# shield.net
KiCad netlist of a schematic drawn in EAGLE
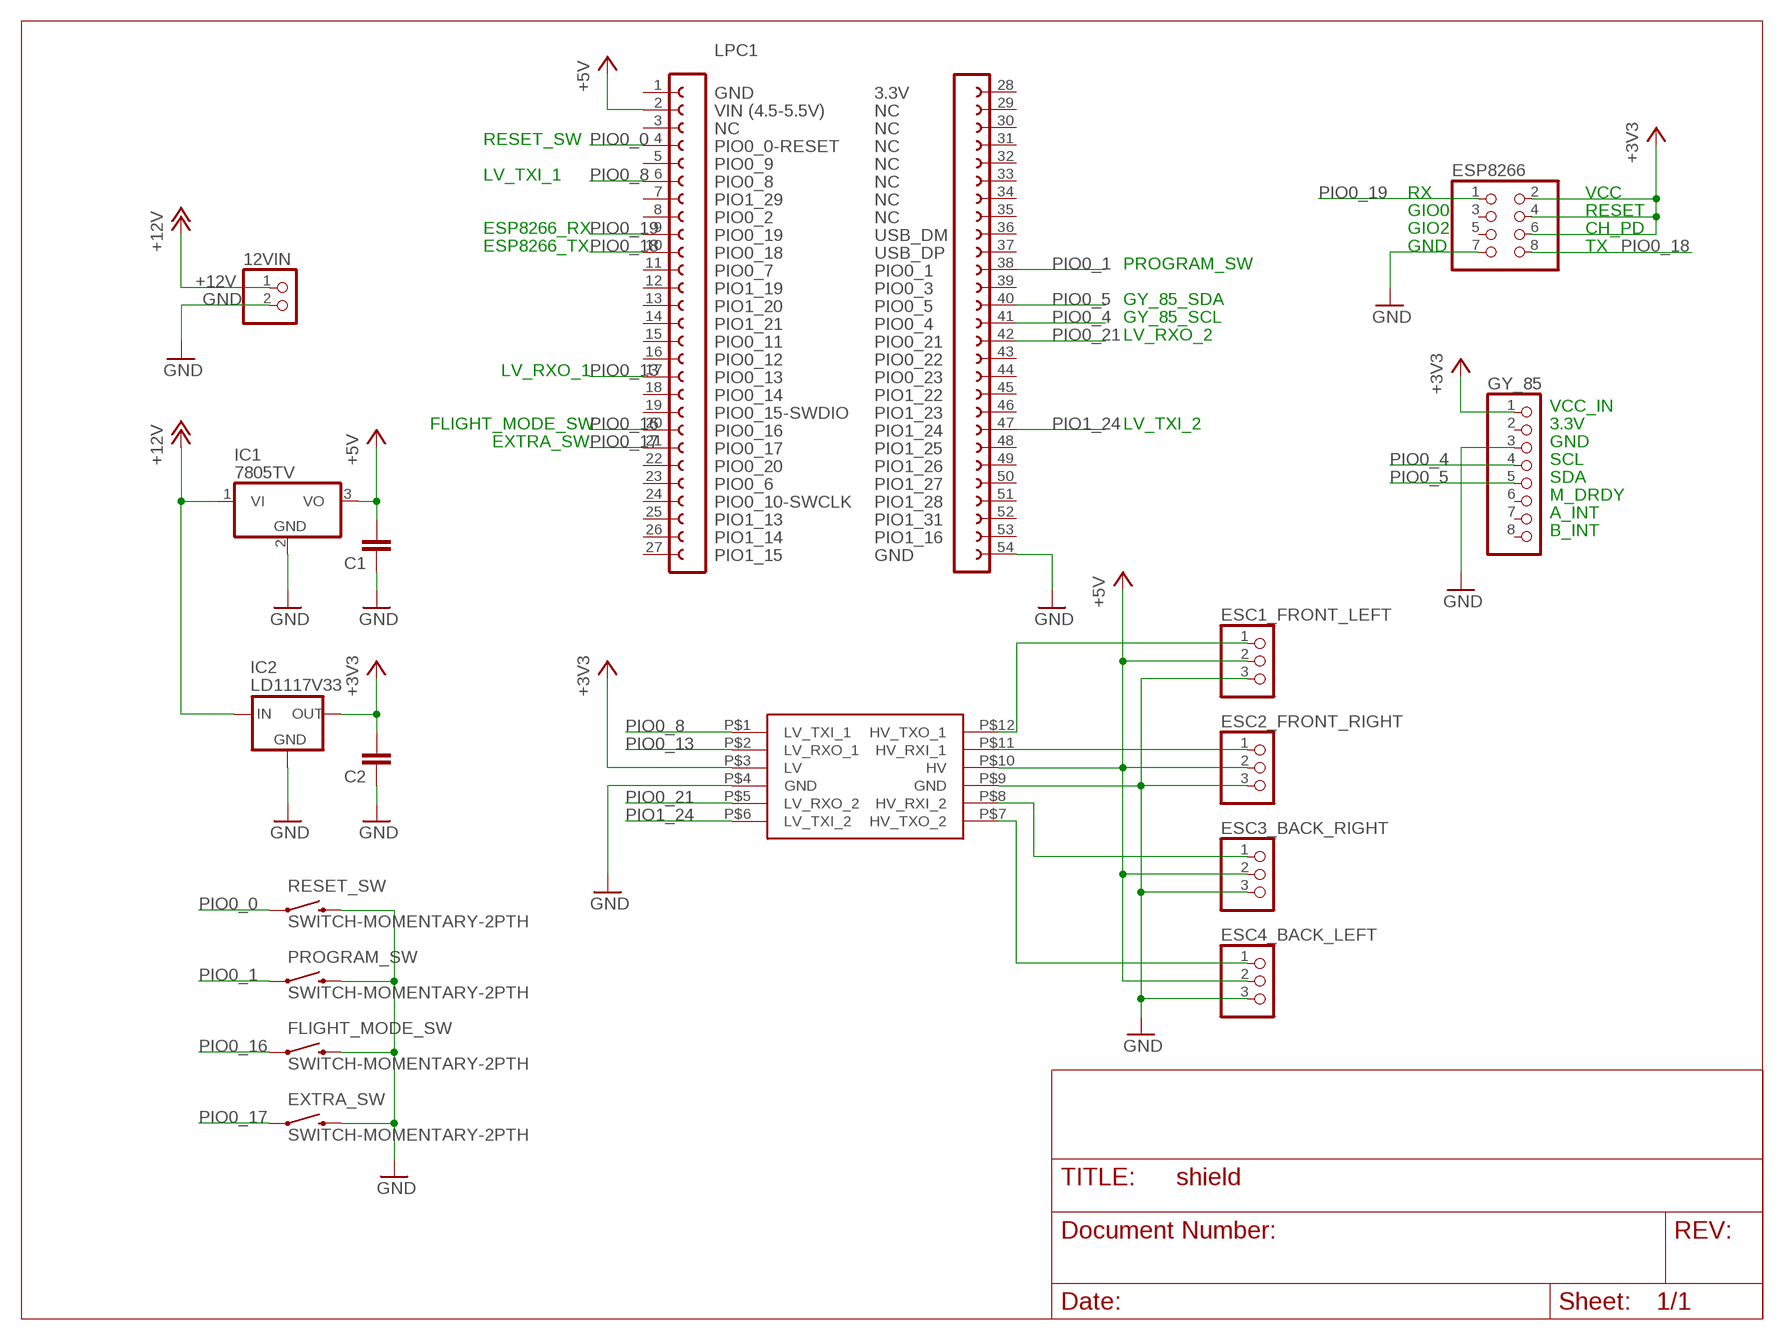
[diagram p0: schematic, sheet 1]

(export (version "E")
  (design (tool "Eeschema 10.0.6"))
  (components
    (comp (ref "12VIN")
      (value "PINHD-1X2")
      (footprint "eagle-import:1X02")
      (libsource (lib "eagle-import") (part "PINHD-1X2"))
    )
    (comp (ref "C1")
      (value "C-EU025-024X044")
      (footprint "eagle-import:C025-024X044")
      (libsource (lib "eagle-import") (part "C-EU025-024X044"))
    )
    (comp (ref "C2")
      (value "C-EU025-024X044")
      (footprint "eagle-import:C025-024X044")
      (libsource (lib "eagle-import") (part "C-EU025-024X044"))
    )
    (comp (ref "ESC1_FRONT_LEFT")
      (value "PINHD-1X3")
      (footprint "eagle-import:1X03")
      (libsource (lib "eagle-import") (part "PINHD-1X3"))
    )
    (comp (ref "ESC2_FRONT_RIGHT")
      (value "PINHD-1X3")
      (footprint "eagle-import:1X03")
      (libsource (lib "eagle-import") (part "PINHD-1X3"))
    )
    (comp (ref "ESC3_BACK_RIGHT")
      (value "PINHD-1X3")
      (footprint "eagle-import:1X03")
      (libsource (lib "eagle-import") (part "PINHD-1X3"))
    )
    (comp (ref "ESC4_BACK_LEFT")
      (value "PINHD-1X3")
      (footprint "eagle-import:1X03")
      (libsource (lib "eagle-import") (part "PINHD-1X3"))
    )
    (comp (ref "ESP8266")
      (value "PINHD-2X4")
      (footprint "eagle-import:2X04")
      (libsource (lib "eagle-import") (part "PINHD-2X4"))
    )
    (comp (ref "EXTRA_SW")
      (value "SWITCH-MOMENTARY-2PTH")
      (footprint "eagle-import:TACTILE-PTH")
      (libsource (lib "eagle-import") (part "SWITCH-MOMENTARY-2PTH"))
    )
    (comp (ref "FLIGHT_MODE_SW")
      (value "SWITCH-MOMENTARY-2PTH")
      (footprint "eagle-import:TACTILE-PTH")
      (libsource (lib "eagle-import") (part "SWITCH-MOMENTARY-2PTH"))
    )
    (comp (ref "GY_85")
      (value "PINHD-1X8")
      (footprint "eagle-import:1X08")
      (libsource (lib "eagle-import") (part "PINHD-1X8"))
    )
    (comp (ref "IC1")
      (value "7805TV")
      (footprint "eagle-import:TO220V")
      (libsource (lib "eagle-import") (part "78TV05"))
    )
    (comp (ref "IC2")
      (value "LD1117V33")
      (footprint "eagle-import:LD1117V33")
      (libsource (lib "eagle-import") (part "LD1117V33"))
    )
    (comp (ref "LPC1")
      (value "LPCXPRESSO_LPC11U14")
      (footprint "eagle-import:LPCXPRESSO_LPC11U14")
      (libsource (lib "eagle-import") (part "LPCXPRESSO_LPC11U14"))
    )
    (comp (ref "PROGRAM_SW")
      (value "SWITCH-MOMENTARY-2PTH")
      (footprint "eagle-import:TACTILE-PTH")
      (libsource (lib "eagle-import") (part "SWITCH-MOMENTARY-2PTH"))
    )
    (comp (ref "RESET_SW")
      (value "SWITCH-MOMENTARY-2PTH")
      (footprint "eagle-import:TACTILE-PTH")
      (libsource (lib "eagle-import") (part "SWITCH-MOMENTARY-2PTH"))
    )
    (comp (ref "U$1")
      (value "LOGIC_LEVEL_CONVERTER")
      (footprint "eagle-import:LOGIC_LEVEL_CONVERTER")
      (libsource (lib "eagle-import") (part "LOGIC_LEVEL_CONVERTER"))
    )
  )
  (nets
    (net (code "1") (name "+3V3") (class "Default")
      (node (ref "C2") (pin "2") (pinfunction "2_2") (pintype "passive"))
      (node (ref "ESP8266") (pin "2") (pinfunction "2_2") (pintype "passive"))
      (node (ref "ESP8266") (pin "4") (pinfunction "4_4") (pintype "passive"))
      (node (ref "ESP8266") (pin "6") (pinfunction "6_6") (pintype "passive"))
      (node (ref "GY_85") (pin "1") (pinfunction "1_1") (pintype "passive"))
      (node (ref "IC2") (pin "OUT") (pinfunction "OUT_OUT") (pintype "output"))
      (node (ref "U$1") (pin "P$3") (pinfunction "LV_P$3") (pintype "bidirectional"))
    )
    (net (code "2") (name "+5V") (class "Default")
      (node (ref "C1") (pin "2") (pinfunction "2_2") (pintype "passive"))
      (node (ref "ESC1_FRONT_LEFT") (pin "2") (pinfunction "2_2") (pintype "passive"))
      (node (ref "ESC2_FRONT_RIGHT") (pin "2") (pinfunction "2_2") (pintype "passive"))
      (node (ref "ESC3_BACK_RIGHT") (pin "2") (pinfunction "2_2") (pintype "passive"))
      (node (ref "ESC4_BACK_LEFT") (pin "2") (pinfunction "2_2") (pintype "passive"))
      (node (ref "IC1") (pin "3") (pinfunction "VO_3") (pintype "passive"))
      (node (ref "LPC1") (pin "2") (pinfunction "2_2") (pintype "passive"))
      (node (ref "U$1") (pin "P$10") (pinfunction "HV_P$10") (pintype "bidirectional"))
    )
    (net (code "3") (name "+12V") (class "Default")
      (node (ref "12VIN") (pin "1") (pinfunction "1_1") (pintype "passive"))
      (node (ref "IC1") (pin "1") (pinfunction "VI_1") (pintype "input"))
      (node (ref "IC2") (pin "IN") (pinfunction "IN_IN") (pintype "input"))
    )
    (net (code "4") (name "/PIO0_0") (class "Default")
      (node (ref "LPC1") (pin "4") (pinfunction "4_4") (pintype "passive"))
      (node (ref "RESET_SW") (pin "1") (pinfunction "1_1") (pintype "passive"))
    )
    (net (code "5") (name "/PIO0_1") (class "Default")
      (node (ref "LPC1") (pin "38") (pinfunction "38_38") (pintype "passive"))
      (node (ref "PROGRAM_SW") (pin "1") (pinfunction "1_1") (pintype "passive"))
    )
    (net (code "6") (name "/PIO0_4") (class "Default")
      (node (ref "GY_85") (pin "4") (pinfunction "4_4") (pintype "passive"))
      (node (ref "LPC1") (pin "41") (pinfunction "41_41") (pintype "passive"))
    )
    (net (code "7") (name "/PIO0_5") (class "Default")
      (node (ref "GY_85") (pin "5") (pinfunction "5_5") (pintype "passive"))
      (node (ref "LPC1") (pin "40") (pinfunction "40_40") (pintype "passive"))
    )
    (net (code "8") (name "/PIO0_8") (class "Default")
      (node (ref "LPC1") (pin "6") (pinfunction "6_6") (pintype "passive"))
      (node (ref "U$1") (pin "P$1") (pinfunction "LV_TXI_1_P$1") (pintype "bidirectional"))
    )
    (net (code "9") (name "/PIO0_13") (class "Default")
      (node (ref "LPC1") (pin "17") (pinfunction "17_17") (pintype "passive"))
      (node (ref "U$1") (pin "P$2") (pinfunction "LV_RXO_1_P$2") (pintype "bidirectional"))
    )
    (net (code "10") (name "/PIO0_16") (class "Default")
      (node (ref "FLIGHT_MODE_SW") (pin "1") (pinfunction "1_1") (pintype "passive"))
      (node (ref "LPC1") (pin "20") (pinfunction "20_20") (pintype "passive"))
    )
    (net (code "11") (name "/PIO0_17") (class "Default")
      (node (ref "EXTRA_SW") (pin "1") (pinfunction "1_1") (pintype "passive"))
      (node (ref "LPC1") (pin "21") (pinfunction "21_21") (pintype "passive"))
    )
    (net (code "12") (name "/PIO0_18") (class "Default")
      (node (ref "ESP8266") (pin "8") (pinfunction "8_8") (pintype "passive"))
      (node (ref "LPC1") (pin "10") (pinfunction "10_10") (pintype "passive"))
    )
    (net (code "13") (name "/PIO0_19") (class "Default")
      (node (ref "ESP8266") (pin "1") (pinfunction "1_1") (pintype "passive"))
      (node (ref "LPC1") (pin "9") (pinfunction "9_9") (pintype "passive"))
    )
    (net (code "14") (name "/PIO0_21") (class "Default")
      (node (ref "LPC1") (pin "42") (pinfunction "42_42") (pintype "passive"))
      (node (ref "U$1") (pin "P$5") (pinfunction "LV_RXO_2_P$5") (pintype "bidirectional"))
    )
    (net (code "15") (name "/PIO1_24") (class "Default")
      (node (ref "LPC1") (pin "47") (pinfunction "47_47") (pintype "passive"))
      (node (ref "U$1") (pin "P$6") (pinfunction "LV_TXI_2_P$6") (pintype "bidirectional"))
    )
    (net (code "16") (name "GND") (class "Default")
      (node (ref "12VIN") (pin "2") (pinfunction "2_2") (pintype "passive"))
      (node (ref "C1") (pin "1") (pinfunction "1_1") (pintype "passive"))
      (node (ref "C2") (pin "1") (pinfunction "1_1") (pintype "passive"))
      (node (ref "ESC1_FRONT_LEFT") (pin "3") (pinfunction "3_3") (pintype "passive"))
      (node (ref "ESC2_FRONT_RIGHT") (pin "3") (pinfunction "3_3") (pintype "passive"))
      (node (ref "ESC3_BACK_RIGHT") (pin "3") (pinfunction "3_3") (pintype "passive"))
      (node (ref "ESC4_BACK_LEFT") (pin "3") (pinfunction "3_3") (pintype "passive"))
      (node (ref "ESP8266") (pin "7") (pinfunction "7_7") (pintype "passive"))
      (node (ref "EXTRA_SW") (pin "3") (pinfunction "2_3") (pintype "passive"))
      (node (ref "FLIGHT_MODE_SW") (pin "3") (pinfunction "2_3") (pintype "passive"))
      (node (ref "GY_85") (pin "3") (pinfunction "3_3") (pintype "passive"))
      (node (ref "IC1") (pin "2") (pinfunction "GND_2") (pintype "passive"))
      (node (ref "IC2") (pin "GND") (pinfunction "GND_GND") (pintype "input"))
      (node (ref "LPC1") (pin "54") (pinfunction "54_54") (pintype "passive"))
      (node (ref "PROGRAM_SW") (pin "3") (pinfunction "2_3") (pintype "passive"))
      (node (ref "RESET_SW") (pin "3") (pinfunction "2_3") (pintype "passive"))
      (node (ref "U$1") (pin "P$4") (pinfunction "GND_P$4") (pintype "bidirectional"))
      (node (ref "U$1") (pin "P$9") (pinfunction "GND_P$9") (pintype "bidirectional"))
    )
    (net (code "17") (name "Net-(U$1-HV_RXI_1)") (class "Default")
      (node (ref "ESC2_FRONT_RIGHT") (pin "1") (pinfunction "1_1") (pintype "passive"))
      (node (ref "U$1") (pin "P$11") (pinfunction "HV_RXI_1_P$11") (pintype "bidirectional"))
    )
    (net (code "18") (name "Net-(U$1-HV_RXI_2)") (class "Default")
      (node (ref "ESC3_BACK_RIGHT") (pin "1") (pinfunction "1_1") (pintype "passive"))
      (node (ref "U$1") (pin "P$8") (pinfunction "HV_RXI_2_P$8") (pintype "bidirectional"))
    )
    (net (code "19") (name "Net-(U$1-HV_TXO_1)") (class "Default")
      (node (ref "ESC1_FRONT_LEFT") (pin "1") (pinfunction "1_1") (pintype "passive"))
      (node (ref "U$1") (pin "P$12") (pinfunction "HV_TXO_1_P$12") (pintype "bidirectional"))
    )
    (net (code "20") (name "Net-(U$1-HV_TXO_2)") (class "Default")
      (node (ref "ESC4_BACK_LEFT") (pin "1") (pinfunction "1_1") (pintype "passive"))
      (node (ref "U$1") (pin "P$7") (pinfunction "HV_TXO_2_P$7") (pintype "bidirectional"))
    )
    (net (code "21") (name "unconnected-(ESP8266-Pad3)") (class "Default")
      (node (ref "ESP8266") (pin "3") (pinfunction "3_3") (pintype "passive"))
    )
    (net (code "22") (name "unconnected-(ESP8266-Pad5)") (class "Default")
      (node (ref "ESP8266") (pin "5") (pinfunction "5_5") (pintype "passive"))
    )
    (net (code "23") (name "unconnected-(GY_85-Pad2)") (class "Default")
      (node (ref "GY_85") (pin "2") (pinfunction "2_2") (pintype "passive"))
    )
    (net (code "24") (name "unconnected-(GY_85-Pad6)") (class "Default")
      (node (ref "GY_85") (pin "6") (pinfunction "6_6") (pintype "passive"))
    )
    (net (code "25") (name "unconnected-(GY_85-Pad7)") (class "Default")
      (node (ref "GY_85") (pin "7") (pinfunction "7_7") (pintype "passive"))
    )
    (net (code "26") (name "unconnected-(GY_85-Pad8)") (class "Default")
      (node (ref "GY_85") (pin "8") (pinfunction "8_8") (pintype "passive"))
    )
    (net (code "27") (name "unconnected-(LPC1-Pad1)") (class "Default")
      (node (ref "LPC1") (pin "1") (pinfunction "1_1") (pintype "passive"))
    )
    (net (code "28") (name "unconnected-(LPC1-Pad3)") (class "Default")
      (node (ref "LPC1") (pin "3") (pinfunction "3_3") (pintype "passive"))
    )
    (net (code "29") (name "unconnected-(LPC1-Pad5)") (class "Default")
      (node (ref "LPC1") (pin "5") (pinfunction "5_5") (pintype "passive"))
    )
    (net (code "30") (name "unconnected-(LPC1-Pad7)") (class "Default")
      (node (ref "LPC1") (pin "7") (pinfunction "7_7") (pintype "passive"))
    )
    (net (code "31") (name "unconnected-(LPC1-Pad8)") (class "Default")
      (node (ref "LPC1") (pin "8") (pinfunction "8_8") (pintype "passive"))
    )
    (net (code "32") (name "unconnected-(LPC1-Pad11)") (class "Default")
      (node (ref "LPC1") (pin "11") (pinfunction "11_11") (pintype "passive"))
    )
    (net (code "33") (name "unconnected-(LPC1-Pad12)") (class "Default")
      (node (ref "LPC1") (pin "12") (pinfunction "12_12") (pintype "passive"))
    )
    (net (code "34") (name "unconnected-(LPC1-Pad13)") (class "Default")
      (node (ref "LPC1") (pin "13") (pinfunction "13_13") (pintype "passive"))
    )
    (net (code "35") (name "unconnected-(LPC1-Pad14)") (class "Default")
      (node (ref "LPC1") (pin "14") (pinfunction "14_14") (pintype "passive"))
    )
    (net (code "36") (name "unconnected-(LPC1-Pad15)") (class "Default")
      (node (ref "LPC1") (pin "15") (pinfunction "15_15") (pintype "passive"))
    )
    (net (code "37") (name "unconnected-(LPC1-Pad16)") (class "Default")
      (node (ref "LPC1") (pin "16") (pinfunction "16_16") (pintype "passive"))
    )
    (net (code "38") (name "unconnected-(LPC1-Pad18)") (class "Default")
      (node (ref "LPC1") (pin "18") (pinfunction "18_18") (pintype "passive"))
    )
    (net (code "39") (name "unconnected-(LPC1-Pad19)") (class "Default")
      (node (ref "LPC1") (pin "19") (pinfunction "19_19") (pintype "passive"))
    )
    (net (code "40") (name "unconnected-(LPC1-Pad22)") (class "Default")
      (node (ref "LPC1") (pin "22") (pinfunction "22_22") (pintype "passive"))
    )
    (net (code "41") (name "unconnected-(LPC1-Pad23)") (class "Default")
      (node (ref "LPC1") (pin "23") (pinfunction "23_23") (pintype "passive"))
    )
    (net (code "42") (name "unconnected-(LPC1-Pad24)") (class "Default")
      (node (ref "LPC1") (pin "24") (pinfunction "24_24") (pintype "passive"))
    )
    (net (code "43") (name "unconnected-(LPC1-Pad25)") (class "Default")
      (node (ref "LPC1") (pin "25") (pinfunction "25_25") (pintype "passive"))
    )
    (net (code "44") (name "unconnected-(LPC1-Pad26)") (class "Default")
      (node (ref "LPC1") (pin "26") (pinfunction "26_26") (pintype "passive"))
    )
    (net (code "45") (name "unconnected-(LPC1-Pad27)") (class "Default")
      (node (ref "LPC1") (pin "27") (pinfunction "27_27") (pintype "passive"))
    )
    (net (code "46") (name "unconnected-(LPC1-Pad28)") (class "Default")
      (node (ref "LPC1") (pin "28") (pinfunction "28_28") (pintype "passive"))
    )
    (net (code "47") (name "unconnected-(LPC1-Pad29)") (class "Default")
      (node (ref "LPC1") (pin "29") (pinfunction "29_29") (pintype "passive"))
    )
    (net (code "48") (name "unconnected-(LPC1-Pad30)") (class "Default")
      (node (ref "LPC1") (pin "30") (pinfunction "30_30") (pintype "passive"))
    )
    (net (code "49") (name "unconnected-(LPC1-Pad31)") (class "Default")
      (node (ref "LPC1") (pin "31") (pinfunction "31_31") (pintype "passive"))
    )
    (net (code "50") (name "unconnected-(LPC1-Pad32)") (class "Default")
      (node (ref "LPC1") (pin "32") (pinfunction "32_32") (pintype "passive"))
    )
    (net (code "51") (name "unconnected-(LPC1-Pad33)") (class "Default")
      (node (ref "LPC1") (pin "33") (pinfunction "33_33") (pintype "passive"))
    )
    (net (code "52") (name "unconnected-(LPC1-Pad34)") (class "Default")
      (node (ref "LPC1") (pin "34") (pinfunction "34_34") (pintype "passive"))
    )
    (net (code "53") (name "unconnected-(LPC1-Pad35)") (class "Default")
      (node (ref "LPC1") (pin "35") (pinfunction "35_35") (pintype "passive"))
    )
    (net (code "54") (name "unconnected-(LPC1-Pad36)") (class "Default")
      (node (ref "LPC1") (pin "36") (pinfunction "36_36") (pintype "passive"))
    )
    (net (code "55") (name "unconnected-(LPC1-Pad37)") (class "Default")
      (node (ref "LPC1") (pin "37") (pinfunction "37_37") (pintype "passive"))
    )
    (net (code "56") (name "unconnected-(LPC1-Pad39)") (class "Default")
      (node (ref "LPC1") (pin "39") (pinfunction "39_39") (pintype "passive"))
    )
    (net (code "57") (name "unconnected-(LPC1-Pad43)") (class "Default")
      (node (ref "LPC1") (pin "43") (pinfunction "43_43") (pintype "passive"))
    )
    (net (code "58") (name "unconnected-(LPC1-Pad44)") (class "Default")
      (node (ref "LPC1") (pin "44") (pinfunction "44_44") (pintype "passive"))
    )
    (net (code "59") (name "unconnected-(LPC1-Pad45)") (class "Default")
      (node (ref "LPC1") (pin "45") (pinfunction "45_45") (pintype "passive"))
    )
    (net (code "60") (name "unconnected-(LPC1-Pad46)") (class "Default")
      (node (ref "LPC1") (pin "46") (pinfunction "46_46") (pintype "passive"))
    )
    (net (code "61") (name "unconnected-(LPC1-Pad48)") (class "Default")
      (node (ref "LPC1") (pin "48") (pinfunction "48_48") (pintype "passive"))
    )
    (net (code "62") (name "unconnected-(LPC1-Pad49)") (class "Default")
      (node (ref "LPC1") (pin "49") (pinfunction "49_49") (pintype "passive"))
    )
    (net (code "63") (name "unconnected-(LPC1-Pad50)") (class "Default")
      (node (ref "LPC1") (pin "50") (pinfunction "50_50") (pintype "passive"))
    )
    (net (code "64") (name "unconnected-(LPC1-Pad51)") (class "Default")
      (node (ref "LPC1") (pin "51") (pinfunction "51_51") (pintype "passive"))
    )
    (net (code "65") (name "unconnected-(LPC1-Pad52)") (class "Default")
      (node (ref "LPC1") (pin "52") (pinfunction "52_52") (pintype "passive"))
    )
    (net (code "66") (name "unconnected-(LPC1-Pad53)") (class "Default")
      (node (ref "LPC1") (pin "53") (pinfunction "53_53") (pintype "passive"))
    )
  )
)
